# STM32F4.net
KiCad netlist of a schematic drawn in Altium Designer
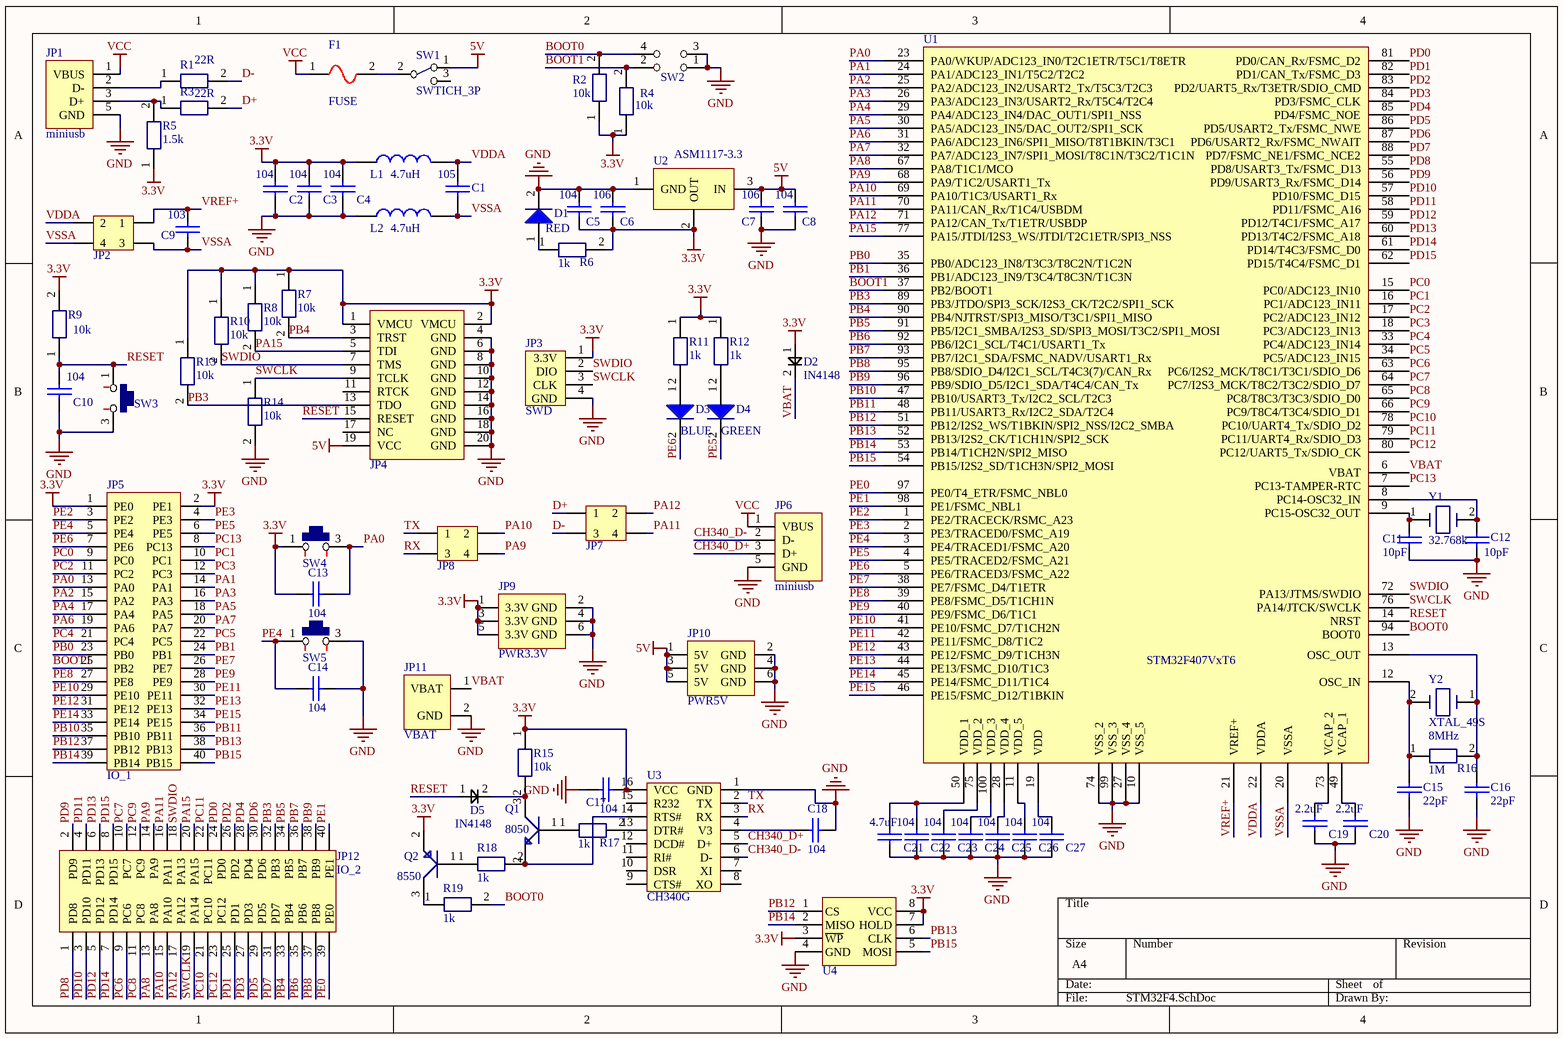
[diagram p0: STM32F4.SchDoc]

(export (version "E")
  (design (tool "Eeschema 10.0.6"))
  (components
    (comp (ref "C1")
      (value "0805c")
      (footprint "0805C")
      (fields (field (name "ALTIUM_UNNAMED_3") "105"))
      (libsource (lib "CORE") (part "0805c"))
    )
    (comp (ref "C2")
      (value "0805c")
      (footprint "0805C")
      (fields (field (name "ALTIUM_UNNAMED_2") "104"))
      (libsource (lib "CORE") (part "0805c"))
    )
    (comp (ref "C3")
      (value "0805c")
      (footprint "0805C")
      (fields (field (name "ALTIUM_UNNAMED_2") "104"))
      (libsource (lib "CORE") (part "0805c"))
    )
    (comp (ref "C4")
      (value "0805c")
      (footprint "0805C")
      (fields (field (name "ALTIUM_UNNAMED_2") "104"))
      (libsource (lib "CORE") (part "0805c"))
    )
    (comp (ref "C5")
      (value "0805c")
      (footprint "0805C")
      (fields (field (name "ALTIUM_UNNAMED_2") "104"))
      (libsource (lib "CORE") (part "0805c"))
    )
    (comp (ref "C6")
      (value "0805c")
      (footprint "0805C")
      (fields (field (name "ALTIUM_UNNAMED_3") "106"))
      (libsource (lib "CORE") (part "0805c"))
    )
    (comp (ref "C7")
      (value "0805c")
      (footprint "0805C")
      (fields (field (name "ALTIUM_UNNAMED_3") "106"))
      (libsource (lib "CORE") (part "0805c"))
    )
    (comp (ref "C8")
      (value "0805c")
      (footprint "0805C")
      (fields (field (name "ALTIUM_UNNAMED_2") "104"))
      (libsource (lib "CORE") (part "0805c"))
    )
    (comp (ref "C9")
      (value "0805c")
      (footprint "0805C")
      (fields (field (name "ALTIUM_UNNAMED_2") "103"))
      (libsource (lib "CORE") (part "0805c"))
    )
    (comp (ref "C10")
      (value "0805c")
      (footprint "0805C")
      (fields (field (name "ALTIUM_UNNAMED_2") "104"))
      (libsource (lib "CORE") (part "0805c"))
    )
    (comp (ref "C11")
      (value "0805c")
      (footprint "0805C")
      (fields (field (name "ALTIUM_UNNAMED_1") "10pF"))
      (libsource (lib "CORE") (part "0805c"))
    )
    (comp (ref "C12")
      (value "0805c")
      (footprint "0805C")
      (fields (field (name "ALTIUM_UNNAMED_1") "10pF"))
      (libsource (lib "CORE") (part "0805c"))
    )
    (comp (ref "C13")
      (value "0805c")
      (footprint "0805C")
      (fields (field (name "ALTIUM_UNNAMED_2") "104"))
      (libsource (lib "CORE") (part "0805c"))
    )
    (comp (ref "C14")
      (value "0805c")
      (footprint "0805C")
      (fields (field (name "ALTIUM_UNNAMED_2") "104"))
      (libsource (lib "CORE") (part "0805c"))
    )
    (comp (ref "C15")
      (value "0805c")
      (footprint "0805C")
      (fields (field (name "ALTIUM_UNNAMED_1") "22pF"))
      (libsource (lib "CORE") (part "0805c"))
    )
    (comp (ref "C16")
      (value "0805c")
      (footprint "0805C")
      (fields (field (name "ALTIUM_UNNAMED_1") "22pF"))
      (libsource (lib "CORE") (part "0805c"))
    )
    (comp (ref "C17")
      (value "0805c")
      (footprint "0805C")
      (fields (field (name "ALTIUM_UNNAMED_2") "104"))
      (libsource (lib "CORE") (part "0805c"))
    )
    (comp (ref "C18")
      (value "0805c")
      (footprint "0805C")
      (fields (field (name "ALTIUM_UNNAMED_2") "104"))
      (libsource (lib "CORE") (part "0805c"))
    )
    (comp (ref "C19")
      (value "0805c")
      (footprint "0805C")
      (fields (field (name "ALTIUM_UNNAMED_2") "2.2uF"))
      (libsource (lib "CORE") (part "0805c"))
    )
    (comp (ref "C20")
      (value "0805c")
      (footprint "0805C")
      (fields (field (name "ALTIUM_UNNAMED_2") "2.2uF"))
      (libsource (lib "CORE") (part "0805c"))
    )
    (comp (ref "C21")
      (value "0805c")
      (footprint "0805C")
      (fields (field (name "ALTIUM_UNNAMED_2") "4.7uF"))
      (libsource (lib "CORE") (part "0805c"))
    )
    (comp (ref "C22")
      (value "0805c")
      (footprint "0805C")
      (fields (field (name "ALTIUM_UNNAMED_2") "104"))
      (libsource (lib "CORE") (part "0805c"))
    )
    (comp (ref "C23")
      (value "0805c")
      (footprint "0805C")
      (fields (field (name "ALTIUM_UNNAMED_2") "104"))
      (libsource (lib "CORE") (part "0805c"))
    )
    (comp (ref "C24")
      (value "0805c")
      (footprint "0805C")
      (fields (field (name "ALTIUM_UNNAMED_2") "104"))
      (libsource (lib "CORE") (part "0805c"))
    )
    (comp (ref "C25")
      (value "0805c")
      (footprint "0805C")
      (fields (field (name "ALTIUM_UNNAMED_2") "104"))
      (libsource (lib "CORE") (part "0805c"))
    )
    (comp (ref "C26")
      (value "0805c")
      (footprint "0805C")
      (fields (field (name "ALTIUM_UNNAMED_2") "104"))
      (libsource (lib "CORE") (part "0805c"))
    )
    (comp (ref "C27")
      (value "0805c")
      (footprint "0805C")
      (fields (field (name "ALTIUM_UNNAMED_2") "104"))
      (libsource (lib "CORE") (part "0805c"))
    )
    (comp (ref "D1")
      (value "LED")
      (footprint "0805D")
      (fields (field (name "ALTIUM_UNNAMED_1") "RED"))
      (libsource (lib "CORE") (part "LED"))
    )
    (comp (ref "D2")
      (value "0805D")
      (footprint "0805D")
      (fields (field (name "PARAMETER 1") "IN4148"))
      (libsource (lib "CORE") (part "0805D"))
    )
    (comp (ref "D3")
      (value "LED")
      (footprint "0805D")
      (fields (field (name "ALTIUM_UNNAMED_1") "BLUE"))
      (libsource (lib "CORE") (part "LED"))
    )
    (comp (ref "D4")
      (value "LED")
      (footprint "0805D")
      (fields (field (name "ALTIUM_UNNAMED_1") "GREEN"))
      (libsource (lib "CORE") (part "LED"))
    )
    (comp (ref "D5")
      (value "0805D")
      (footprint "0805D")
      (fields (field (name "PARAMETER 1") "IN4148"))
      (libsource (lib "CORE") (part "0805D"))
    )
    (comp (ref "F1") (value "FUSE") (footprint "1206R") (libsource (lib "CORE") (part "FUSE")))
    (comp (ref "JP1") (value "miniusb") (footprint "MINI_USB") (libsource (lib "") (part "miniusb_1")))
    (comp (ref "JP2") (value "2*2") (footprint "CON20VP2R54-2X2TM") (libsource (lib "") (part "2*2_1")))
    (comp (ref "JP3") (value "SWD") (footprint "SWD") (libsource (lib "CORE") (part "SWD")))
    (comp (ref "JP4") (value "JTAG") (footprint "JTAG") (libsource (lib "CORE") (part "JTAG")))
    (comp (ref "JP5") (value "IO_1") (footprint "IO") (libsource (lib "CORE") (part "IO_1")))
    (comp (ref "JP6") (value "miniusb") (footprint "MINI_USB") (libsource (lib "CORE") (part "miniusb")))
    (comp (ref "JP7") (value "2*2") (footprint "CON20VP2R54-2X2TM") (libsource (lib "CORE") (part "2*2")))
    (comp (ref "JP8") (value "2*2") (footprint "CON20VP2R54-2X2TM") (libsource (lib "CORE") (part "2*2")))
    (comp (ref "JP9") (value "PWR3.3V") (footprint "PWR") (libsource (lib "CORE") (part "PWR3.3V")))
    (comp (ref "JP10") (value "PWR5V") (footprint "PWR") (libsource (lib "CORE") (part "PWR5V")))
    (comp (ref "JP11") (value "VBAT") (footprint "VBAT") (libsource (lib "CORE") (part "VBAT")))
    (comp (ref "JP12") (value "IO_2") (footprint "IO") (libsource (lib "CORE") (part "IO_2")))
    (comp (ref "L1")
      (value "0805L")
      (footprint "0805L")
      (fields (field (name "ALTIUM_UNNAMED_1") "4.7uH"))
      (libsource (lib "CORE") (part "0805L"))
    )
    (comp (ref "L2")
      (value "0805L")
      (footprint "0805L")
      (fields (field (name "ALTIUM_UNNAMED_1") "4.7uH"))
      (libsource (lib "CORE") (part "0805L"))
    )
    (comp (ref "Q1") (value "8050") (footprint "SOT23-3") (libsource (lib "CORE") (part "8050")))
    (comp (ref "Q2") (value "8550") (footprint "SOT23-3") (libsource (lib "CORE") (part "8550")))
    (comp (ref "R1")
      (value "0805r")
      (footprint "0805R")
      (fields (field (name "ALTIUM_UNNAMED_4") "22R"))
      (libsource (lib "CORE") (part "0805r"))
    )
    (comp (ref "R2")
      (value "0805r")
      (footprint "0805R")
      (fields (field (name "ALTIUM_UNNAMED_4") "10k"))
      (libsource (lib "CORE") (part "0805r"))
    )
    (comp (ref "R3")
      (value "0805r")
      (footprint "0805R")
      (fields (field (name "ALTIUM_UNNAMED_4") "22R"))
      (libsource (lib "CORE") (part "0805r"))
    )
    (comp (ref "R4")
      (value "0805r")
      (footprint "0805R")
      (fields (field (name "ALTIUM_UNNAMED_4") "10k"))
      (libsource (lib "CORE") (part "0805r"))
    )
    (comp (ref "R5")
      (value "0805r")
      (footprint "0805R")
      (fields (field (name "ALTIUM_UNNAMED_4") "1.5k"))
      (libsource (lib "CORE") (part "0805r"))
    )
    (comp (ref "R6")
      (value "0805r")
      (footprint "0805R")
      (fields (field (name "ALTIUM_UNNAMED_3") "1k"))
      (libsource (lib "CORE") (part "0805r"))
    )
    (comp (ref "R7")
      (value "0805r")
      (footprint "0805R")
      (fields (field (name "ALTIUM_UNNAMED_3") "10k"))
      (libsource (lib "CORE") (part "0805r"))
    )
    (comp (ref "R8")
      (value "0805r")
      (footprint "0805R")
      (fields (field (name "ALTIUM_UNNAMED_3") "10k"))
      (libsource (lib "CORE") (part "0805r"))
    )
    (comp (ref "R9")
      (value "0805r")
      (footprint "0805R")
      (fields (field (name "ALTIUM_UNNAMED_1") "10k"))
      (libsource (lib "CORE") (part "0805r"))
    )
    (comp (ref "R10")
      (value "0805r")
      (footprint "0805R")
      (fields (field (name "ALTIUM_UNNAMED_3") "10k"))
      (libsource (lib "CORE") (part "0805r"))
    )
    (comp (ref "R11")
      (value "0805r")
      (footprint "0805R")
      (fields (field (name "ALTIUM_UNNAMED_3") "1k"))
      (libsource (lib "CORE") (part "0805r"))
    )
    (comp (ref "R12")
      (value "0805r")
      (footprint "0805R")
      (fields (field (name "ALTIUM_UNNAMED_3") "1k"))
      (libsource (lib "CORE") (part "0805r"))
    )
    (comp (ref "R13")
      (value "0805r")
      (footprint "0805R")
      (fields (field (name "ALTIUM_UNNAMED_3") "10k"))
      (libsource (lib "CORE") (part "0805r"))
    )
    (comp (ref "R14")
      (value "0805r")
      (footprint "0805R")
      (fields (field (name "ALTIUM_UNNAMED_3") "10k"))
      (libsource (lib "CORE") (part "0805r"))
    )
    (comp (ref "R15")
      (value "0805r")
      (footprint "0805R")
      (fields (field (name "ALTIUM_UNNAMED_3") "10k"))
      (libsource (lib "CORE") (part "0805r"))
    )
    (comp (ref "R16")
      (value "0805r")
      (footprint "0805R")
      (fields (field (name "ALTIUM_UNNAMED_3") "1M"))
      (libsource (lib "CORE") (part "0805r"))
    )
    (comp (ref "R17")
      (value "0805r")
      (footprint "0805R")
      (fields (field (name "ALTIUM_UNNAMED_3") "1k"))
      (libsource (lib "CORE") (part "0805r"))
    )
    (comp (ref "R18")
      (value "0805r")
      (footprint "0805R")
      (fields (field (name "ALTIUM_UNNAMED_3") "1k"))
      (libsource (lib "CORE") (part "0805r"))
    )
    (comp (ref "R19")
      (value "0805r")
      (footprint "0805R")
      (fields (field (name "ALTIUM_UNNAMED_3") "1k"))
      (libsource (lib "CORE") (part "0805r"))
    )
    (comp (ref "SW1") (value "SWTICH_3P") (footprint "SWITCH_3P") (libsource (lib "CORE") (part "SWTICH_3P")))
    (comp (ref "SW2") (value "SW_BOOT") (footprint "DAIL-SWITCH") (libsource (lib "CORE") (part "SW_BOOT")))
    (comp (ref "SW3") (value "KEY") (footprint "KEY_4P") (libsource (lib "CORE") (part "KEY_4P")))
    (comp (ref "SW4") (value "KEY") (footprint "KEY_4P") (libsource (lib "") (part "KEY_4P_1")))
    (comp (ref "SW5") (value "KEY") (footprint "KEY_4P") (libsource (lib "") (part "KEY_4P_1")))
    (comp (ref "U1")
      (value "STM32F407VxT6")
      (footprint "LQFP-100_M")
      (libsource (lib "STM32F4") (part "STM32F407VxT6"))
    )
    (comp (ref "U2")
      (value "ASM1117-3.3")
      (footprint "SOT223_N")
      (libsource (lib "CORE") (part "ASM1117-3.3"))
    )
    (comp (ref "U3") (value "CH340G") (footprint "SOP16") (libsource (lib "CORE") (part "CH340G")))
    (comp (ref "U4") (value "25Q64") (footprint "SOP8") (libsource (lib "CORE") (part "25Q64")))
    (comp (ref "Y1") (value "32.768k") (footprint "圆柱晶振2*6") (libsource (lib "CORE") (part "圆柱晶振")))
    (comp (ref "Y2")
      (value "XTAL_49S")
      (footprint "XTAL")
      (fields (field (name "ALTIUM_UNNAMED_1") "8MHz"))
      (libsource (lib "CORE") (part "XTAL_49S"))
    )
  )
  (nets
    (net (code "1") (name "/BOOT0") (class "Default")
      (node (ref "R19") (pin "2") (pinfunction "2_2") (pintype "passive"))
      (node (ref "R2") (pin "2") (pinfunction "2_2") (pintype "passive"))
      (node (ref "SW2") (pin "4") (pinfunction "4_4") (pintype "passive"))
      (node (ref "U1") (pin "94") (pinfunction "BOOT0_94") (pintype "passive"))
    )
    (net (code "2") (name "/BOOT1") (class "Default")
      (node (ref "JP5") (pin "25") (pinfunction "PB2_25") (pintype "passive"))
      (node (ref "R4") (pin "2") (pinfunction "2_2") (pintype "passive"))
      (node (ref "SW2") (pin "2") (pinfunction "2_2") (pintype "passive"))
      (node (ref "U1") (pin "37") (pinfunction "PB2/BOOT1_37") (pintype "passive"))
    )
    (net (code "3") (name "/CH340_D+") (class "Default")
      (node (ref "JP6") (pin "3") (pinfunction "D+_3") (pintype "passive"))
      (node (ref "U3") (pin "5") (pinfunction "D+_5") (pintype "passive"))
    )
    (net (code "4") (name "/CH340_D-") (class "Default")
      (node (ref "JP6") (pin "2") (pinfunction "D-_2") (pintype "passive"))
      (node (ref "U3") (pin "6") (pinfunction "D-_6") (pintype "passive"))
    )
    (net (code "5") (name "/D+") (class "Default")
      (node (ref "JP7") (pin "1") (pinfunction "1_1") (pintype "passive"))
      (node (ref "R3") (pin "2") (pinfunction "2_2") (pintype "passive"))
    )
    (net (code "6") (name "/D-") (class "Default")
      (node (ref "JP7") (pin "3") (pinfunction "3_3") (pintype "passive"))
      (node (ref "R1") (pin "2") (pinfunction "2_2") (pintype "passive"))
    )
    (net (code "7") (name "/PA0") (class "Default")
      (node (ref "C13") (pin "2") (pinfunction "2_2") (pintype "passive"))
      (node (ref "JP5") (pin "13") (pinfunction "PA0_13") (pintype "passive"))
      (node (ref "SW4") (pin "3") (pintype "passive"))
      (node (ref "U1") (pin "23") (pinfunction "PA0/WKUP/ADC123_IN0/T2C1ETR/T5C1/T8ETR_23") (pintype "passive"))
    )
    (net (code "8") (name "/PA1") (class "Default")
      (node (ref "JP5") (pin "14") (pinfunction "PA1_14") (pintype "passive"))
      (node (ref "U1") (pin "24") (pinfunction "PA1/ADC123_IN1/T5C2/T2C2_24") (pintype "passive"))
    )
    (net (code "9") (name "/PA2") (class "Default")
      (node (ref "JP5") (pin "15") (pinfunction "PA2_15") (pintype "passive"))
      (node (ref "U1") (pin "25") (pinfunction "PA2/ADC123_IN2/USART2_Tx/T5C3/T2C3_25") (pintype "passive"))
    )
    (net (code "10") (name "/PA3") (class "Default")
      (node (ref "JP5") (pin "16") (pinfunction "PA3_16") (pintype "passive"))
      (node (ref "U1") (pin "26") (pinfunction "PA3/ADC123_IN3/USART2_Rx/T5C4/T2C4_26") (pintype "passive"))
    )
    (net (code "11") (name "/PA4") (class "Default")
      (node (ref "JP5") (pin "17") (pinfunction "PA4_17") (pintype "passive"))
      (node (ref "U1") (pin "29") (pinfunction "PA4/ADC123_IN4/DAC_OUT1/SPI1_NSS_29") (pintype "passive"))
    )
    (net (code "12") (name "/PA5") (class "Default")
      (node (ref "JP5") (pin "18") (pinfunction "PA5_18") (pintype "passive"))
      (node (ref "U1") (pin "30") (pinfunction "PA5/ADC123_IN5/DAC_OUT2/SPI1_SCK_30") (pintype "passive"))
    )
    (net (code "13") (name "/PA6") (class "Default")
      (node (ref "JP5") (pin "19") (pinfunction "PA6_19") (pintype "passive"))
      (node (ref "U1") (pin "31") (pinfunction "PA6/ADC123_IN6/SPI1_MISO/T8T1BKIN/T3C1_31") (pintype "passive"))
    )
    (net (code "14") (name "/PA7") (class "Default")
      (node (ref "JP5") (pin "20") (pinfunction "PA7_20") (pintype "passive"))
      (node (ref "U1") (pin "32") (pinfunction "PA7/ADC123_IN7/SPI1_MOSI/T8C1N/T3C2/T1C1N_32") (pintype "passive"))
    )
    (net (code "15") (name "/PA8") (class "Default")
      (node (ref "JP12") (pin "13") (pinfunction "PA8_13") (pintype "passive"))
      (node (ref "U1") (pin "67") (pinfunction "PA8/T1C1/MCO_67") (pintype "passive"))
    )
    (net (code "16") (name "/PA9") (class "Default")
      (node (ref "JP12") (pin "14") (pinfunction "PA9_14") (pintype "passive"))
      (node (ref "JP8") (pin "4") (pinfunction "4_4") (pintype "passive"))
      (node (ref "U1") (pin "68") (pinfunction "PA9/T1C2/USART1_Tx_68") (pintype "passive"))
    )
    (net (code "17") (name "/PA10") (class "Default")
      (node (ref "JP12") (pin "15") (pinfunction "PA10_15") (pintype "passive"))
      (node (ref "JP8") (pin "2") (pinfunction "2_2") (pintype "passive"))
      (node (ref "U1") (pin "69") (pinfunction "PA10/T1C3/USART1_Rx_69") (pintype "passive"))
    )
    (net (code "18") (name "/PA11") (class "Default")
      (node (ref "JP12") (pin "16") (pinfunction "PA11_16") (pintype "passive"))
      (node (ref "JP7") (pin "4") (pinfunction "4_4") (pintype "passive"))
      (node (ref "U1") (pin "70") (pinfunction "PA11/CAN_Rx/T1C4/USBDM_70") (pintype "passive"))
    )
    (net (code "19") (name "/PA12") (class "Default")
      (node (ref "JP12") (pin "17") (pinfunction "PA12_17") (pintype "passive"))
      (node (ref "JP7") (pin "2") (pinfunction "2_2") (pintype "passive"))
      (node (ref "U1") (pin "71") (pinfunction "PA12/CAN_Tx/T1ETR/USBDP_71") (pintype "passive"))
    )
    (net (code "20") (name "/PA15") (class "Default")
      (node (ref "JP12") (pin "20") (pinfunction "PA15_20") (pintype "passive"))
      (node (ref "JP4") (pin "5") (pinfunction "TDI_5") (pintype "passive"))
      (node (ref "R8") (pin "2") (pinfunction "2_2") (pintype "passive"))
      (node (ref "U1") (pin "77") (pinfunction "PA15/JTDI/I2S3_WS/JTDI/T2C1ETR/SPI3_NSS_77") (pintype "passive"))
    )
    (net (code "21") (name "/PB0") (class "Default")
      (node (ref "JP5") (pin "23") (pinfunction "PB0_23") (pintype "passive"))
      (node (ref "U1") (pin "35") (pinfunction "PB0/ADC123_IN8/T3C3/T8C2N/T1C2N_35") (pintype "passive"))
    )
    (net (code "22") (name "/PB1") (class "Default")
      (node (ref "JP5") (pin "24") (pinfunction "PB1_24") (pintype "passive"))
      (node (ref "U1") (pin "36") (pinfunction "PB1/ADC123_IN9/T3C4/T8C3N/T1C3N_36") (pintype "passive"))
    )
    (net (code "23") (name "/PB3") (class "Default")
      (node (ref "JP12") (pin "32") (pinfunction "PB3_32") (pintype "passive"))
      (node (ref "JP4") (pin "13") (pinfunction "TDO_13") (pintype "passive"))
      (node (ref "R13") (pin "2") (pinfunction "2_2") (pintype "passive"))
      (node (ref "U1") (pin "89") (pinfunction "PB3/JTDO/SPI3_SCK/I2S3_CK/T2C2/SPI1_SCK_89") (pintype "passive"))
    )
    (net (code "24") (name "/PB4") (class "Default")
      (node (ref "JP12") (pin "33") (pinfunction "PB4_33") (pintype "passive"))
      (node (ref "JP4") (pin "3") (pinfunction "TRST_3") (pintype "passive"))
      (node (ref "R7") (pin "2") (pinfunction "2_2") (pintype "passive"))
      (node (ref "U1") (pin "90") (pinfunction "PB4/NJTRST/SPI3_MISO/T3C1/SPI1_MISO_90") (pintype "passive"))
    )
    (net (code "25") (name "/PB5") (class "Default")
      (node (ref "JP12") (pin "34") (pinfunction "PB5_34") (pintype "passive"))
      (node (ref "U1") (pin "91") (pinfunction "PB5/I2C1_SMBA/I2S3_SD/SPI3_MOSI/T3C2/SPI1_MOSI_91") (pintype "passive"))
    )
    (net (code "26") (name "/PB6") (class "Default")
      (node (ref "JP12") (pin "35") (pinfunction "PB6_35") (pintype "passive"))
      (node (ref "U1") (pin "92") (pinfunction "PB6/I2C1_SCL/T4C1/USART1_Tx_92") (pintype "passive"))
    )
    (net (code "27") (name "/PB7") (class "Default")
      (node (ref "JP12") (pin "36") (pinfunction "PB7_36") (pintype "passive"))
      (node (ref "U1") (pin "93") (pinfunction "PB7/I2C1_SDA/FSMC_NADV/USART1_Rx_93") (pintype "passive"))
    )
    (net (code "28") (name "/PB8") (class "Default")
      (node (ref "JP12") (pin "37") (pinfunction "PB8_37") (pintype "passive"))
      (node (ref "U1") (pin "95") (pinfunction "PB8/SDIO_D4/I2C1_SCL/T4C3(7)/CAN_Rx_95") (pintype "passive"))
    )
    (net (code "29") (name "/PB9") (class "Default")
      (node (ref "JP12") (pin "38") (pinfunction "PB9_38") (pintype "passive"))
      (node (ref "U1") (pin "96") (pinfunction "PB9/SDIO_D5/I2C1_SDA/T4C4/CAN_Tx_96") (pintype "passive"))
    )
    (net (code "30") (name "/PB10") (class "Default")
      (node (ref "JP5") (pin "35") (pinfunction "PB10_35") (pintype "passive"))
      (node (ref "U1") (pin "47") (pinfunction "PB10/USART3_Tx/I2C2_SCL/T2C3_47") (pintype "passive"))
    )
    (net (code "31") (name "/PB11") (class "Default")
      (node (ref "JP5") (pin "36") (pinfunction "PB11_36") (pintype "passive"))
      (node (ref "U1") (pin "48") (pinfunction "PB11/USART3_Rx/I2C2_SDA/T2C4_48") (pintype "passive"))
    )
    (net (code "32") (name "/PB12") (class "Default")
      (node (ref "JP5") (pin "37") (pinfunction "PB12_37") (pintype "passive"))
      (node (ref "U1") (pin "51") (pinfunction "PB12/I2S2_WS/T1BKIN/SPI2_NSS/I2C2_SMBA_51") (pintype "passive"))
      (node (ref "U4") (pin "1") (pinfunction "CS_1") (pintype "passive"))
    )
    (net (code "33") (name "/PB13") (class "Default")
      (node (ref "JP5") (pin "38") (pinfunction "PB13_38") (pintype "passive"))
      (node (ref "U1") (pin "52") (pinfunction "PB13/I2S2_CK/T1CH1N/SPI2_SCK_52") (pintype "passive"))
      (node (ref "U4") (pin "6") (pinfunction "CLK_6") (pintype "passive"))
    )
    (net (code "34") (name "/PB14") (class "Default")
      (node (ref "JP5") (pin "39") (pinfunction "PB14_39") (pintype "passive"))
      (node (ref "U1") (pin "53") (pinfunction "PB14/T1CH2N/SPI2_MISO_53") (pintype "passive"))
      (node (ref "U4") (pin "2") (pinfunction "MISO_2") (pintype "passive"))
    )
    (net (code "35") (name "/PB15") (class "Default")
      (node (ref "JP5") (pin "40") (pinfunction "PB15_40") (pintype "passive"))
      (node (ref "U1") (pin "54") (pinfunction "PB15/I2S2_SD/T1CH3N/SPI2_MOSI_54") (pintype "passive"))
      (node (ref "U4") (pin "5") (pinfunction "MOSI_5") (pintype "passive"))
    )
    (net (code "36") (name "/PC0") (class "Default")
      (node (ref "JP5") (pin "9") (pinfunction "PC0_9") (pintype "passive"))
      (node (ref "U1") (pin "15") (pinfunction "PC0/ADC123_IN10_15") (pintype "passive"))
    )
    (net (code "37") (name "/PC1") (class "Default")
      (node (ref "JP5") (pin "10") (pinfunction "PC1_10") (pintype "passive"))
      (node (ref "U1") (pin "16") (pinfunction "PC1/ADC123_IN11_16") (pintype "passive"))
    )
    (net (code "38") (name "/PC2") (class "Default")
      (node (ref "JP5") (pin "11") (pinfunction "PC2_11") (pintype "passive"))
      (node (ref "U1") (pin "17") (pinfunction "PC2/ADC123_IN12_17") (pintype "passive"))
    )
    (net (code "39") (name "/PC3") (class "Default")
      (node (ref "JP5") (pin "12") (pinfunction "PC3_12") (pintype "passive"))
      (node (ref "U1") (pin "18") (pinfunction "PC3/ADC123_IN13_18") (pintype "passive"))
    )
    (net (code "40") (name "/PC4") (class "Default")
      (node (ref "JP5") (pin "21") (pinfunction "PC4_21") (pintype "passive"))
      (node (ref "U1") (pin "33") (pinfunction "PC4/ADC123_IN14_33") (pintype "passive"))
    )
    (net (code "41") (name "/PC5") (class "Default")
      (node (ref "JP5") (pin "22") (pinfunction "PC5_22") (pintype "passive"))
      (node (ref "U1") (pin "34") (pinfunction "PC5/ADC123_IN15_34") (pintype "passive"))
    )
    (net (code "42") (name "/PC6") (class "Default")
      (node (ref "JP12") (pin "9") (pinfunction "PC6_9") (pintype "passive"))
      (node (ref "U1") (pin "63") (pinfunction "PC6/I2S2_MCK/T8C1/T3C1/SDIO_D6_63") (pintype "passive"))
    )
    (net (code "43") (name "/PC7") (class "Default")
      (node (ref "JP12") (pin "10") (pinfunction "PC7_10") (pintype "passive"))
      (node (ref "U1") (pin "64") (pinfunction "PC7/I2S3_MCK/T8C2/T3C2/SDIO_D7_64") (pintype "passive"))
    )
    (net (code "44") (name "/PC8") (class "Default")
      (node (ref "JP12") (pin "11") (pinfunction "PC8_11") (pintype "passive"))
      (node (ref "U1") (pin "65") (pinfunction "PC8/T8C3/T3C3/SDIO_D0_65") (pintype "passive"))
    )
    (net (code "45") (name "/PC9") (class "Default")
      (node (ref "JP12") (pin "12") (pinfunction "PC9_12") (pintype "passive"))
      (node (ref "U1") (pin "66") (pinfunction "PC9/T8C4/T3C4/SDIO_D1_66") (pintype "passive"))
    )
    (net (code "46") (name "/PC10") (class "Default")
      (node (ref "JP12") (pin "21") (pinfunction "PC10_21") (pintype "passive"))
      (node (ref "U1") (pin "78") (pinfunction "PC10/UART4_Tx/SDIO_D2_78") (pintype "passive"))
    )
    (net (code "47") (name "/PC11") (class "Default")
      (node (ref "JP12") (pin "22") (pinfunction "PC11_22") (pintype "passive"))
      (node (ref "U1") (pin "79") (pinfunction "PC11/UART4_Rx/SDIO_D3_79") (pintype "passive"))
    )
    (net (code "48") (name "/PC12") (class "Default")
      (node (ref "JP12") (pin "23") (pinfunction "PC12_23") (pintype "passive"))
      (node (ref "U1") (pin "80") (pinfunction "PC12/UART5_Tx/SDIO_CK_80") (pintype "passive"))
    )
    (net (code "49") (name "/PC13") (class "Default")
      (node (ref "JP5") (pin "8") (pinfunction "PC13_8") (pintype "passive"))
      (node (ref "U1") (pin "7") (pinfunction "PC13-TAMPER-RTC_7") (pintype "passive"))
    )
    (net (code "50") (name "/PD0") (class "Default")
      (node (ref "JP12") (pin "24") (pinfunction "PD0_24") (pintype "passive"))
      (node (ref "U1") (pin "81") (pinfunction "PD0/CAN_Rx/FSMC_D2_81") (pintype "passive"))
    )
    (net (code "51") (name "/PD1") (class "Default")
      (node (ref "JP12") (pin "25") (pinfunction "PD1_25") (pintype "passive"))
      (node (ref "U1") (pin "82") (pinfunction "PD1/CAN_Tx/FSMC_D3_82") (pintype "passive"))
    )
    (net (code "52") (name "/PD2") (class "Default")
      (node (ref "JP12") (pin "26") (pinfunction "PD2_26") (pintype "passive"))
      (node (ref "U1") (pin "83") (pinfunction "PD2/UART5_Rx/T3ETR/SDIO_CMD_83") (pintype "passive"))
    )
    (net (code "53") (name "/PD3") (class "Default")
      (node (ref "JP12") (pin "27") (pinfunction "PD3_27") (pintype "passive"))
      (node (ref "U1") (pin "84") (pinfunction "PD3/FSMC_CLK_84") (pintype "passive"))
    )
    (net (code "54") (name "/PD4") (class "Default")
      (node (ref "JP12") (pin "28") (pinfunction "PD4_28") (pintype "passive"))
      (node (ref "U1") (pin "85") (pinfunction "PD4/FSMC_NOE_85") (pintype "passive"))
    )
    (net (code "55") (name "/PD5") (class "Default")
      (node (ref "JP12") (pin "29") (pinfunction "PD5_29") (pintype "passive"))
      (node (ref "U1") (pin "86") (pinfunction "PD5/USART2_Tx/FSMC_NWE_86") (pintype "passive"))
    )
    (net (code "56") (name "/PD6") (class "Default")
      (node (ref "JP12") (pin "30") (pinfunction "PD6_30") (pintype "passive"))
      (node (ref "U1") (pin "87") (pinfunction "PD6/USART2_Rx/FSMC_NWAIT_87") (pintype "passive"))
    )
    (net (code "57") (name "/PD7") (class "Default")
      (node (ref "JP12") (pin "31") (pinfunction "PD7_31") (pintype "passive"))
      (node (ref "U1") (pin "88") (pinfunction "PD7/FSMC_NE1/FSMC_NCE2_88") (pintype "passive"))
    )
    (net (code "58") (name "/PD8") (class "Default")
      (node (ref "JP12") (pin "1") (pinfunction "PD8_1") (pintype "passive"))
      (node (ref "U1") (pin "55") (pinfunction "PD8/USART3_Tx/FSMC_D13_55") (pintype "passive"))
    )
    (net (code "59") (name "/PD9") (class "Default")
      (node (ref "JP12") (pin "2") (pinfunction "PD9_2") (pintype "passive"))
      (node (ref "U1") (pin "56") (pinfunction "PD9/USART3_Rx/FSMC_D14_56") (pintype "passive"))
    )
    (net (code "60") (name "/PD10") (class "Default")
      (node (ref "JP12") (pin "3") (pinfunction "PD10_3") (pintype "passive"))
      (node (ref "U1") (pin "57") (pinfunction "PD10/FSMC_D15_57") (pintype "passive"))
    )
    (net (code "61") (name "/PD11") (class "Default")
      (node (ref "JP12") (pin "4") (pinfunction "PD11_4") (pintype "passive"))
      (node (ref "U1") (pin "58") (pinfunction "PD11/FSMC_A16_58") (pintype "passive"))
    )
    (net (code "62") (name "/PD12") (class "Default")
      (node (ref "JP12") (pin "5") (pinfunction "PD12_5") (pintype "passive"))
      (node (ref "U1") (pin "59") (pinfunction "PD12/T4C1/FSMC_A17_59") (pintype "passive"))
    )
    (net (code "63") (name "/PD13") (class "Default")
      (node (ref "JP12") (pin "6") (pinfunction "PD13_6") (pintype "passive"))
      (node (ref "U1") (pin "60") (pinfunction "PD13/T4C2/FSMC_A18_60") (pintype "passive"))
    )
    (net (code "64") (name "/PD14") (class "Default")
      (node (ref "JP12") (pin "7") (pinfunction "PD14_7") (pintype "passive"))
      (node (ref "U1") (pin "61") (pinfunction "PD14/T4C3/FSMC_D0_61") (pintype "passive"))
    )
    (net (code "65") (name "/PD15") (class "Default")
      (node (ref "JP12") (pin "8") (pinfunction "PD15_8") (pintype "passive"))
      (node (ref "U1") (pin "62") (pinfunction "PD15/T4C4/FSMC_D1_62") (pintype "passive"))
    )
    (net (code "66") (name "/PE0") (class "Default")
      (node (ref "JP12") (pin "39") (pinfunction "PE0_39") (pintype "passive"))
      (node (ref "U1") (pin "97") (pinfunction "PE0/T4_ETR/FSMC_NBL0_97") (pintype "passive"))
    )
    (net (code "67") (name "/PE1") (class "Default")
      (node (ref "JP12") (pin "40") (pinfunction "PE1_40") (pintype "passive"))
      (node (ref "U1") (pin "98") (pinfunction "PE1/FSMC_NBL1_98") (pintype "passive"))
    )
    (net (code "68") (name "/PE2") (class "Default")
      (node (ref "JP5") (pin "3") (pinfunction "PE2_3") (pintype "passive"))
      (node (ref "U1") (pin "1") (pinfunction "PE2/TRACECK/RSMC_A23_1") (pintype "passive"))
    )
    (net (code "69") (name "/PE3") (class "Default")
      (node (ref "JP5") (pin "4") (pinfunction "PE3_4") (pintype "passive"))
      (node (ref "U1") (pin "2") (pinfunction "PE3/TRACED0/FSMC_A19_2") (pintype "passive"))
    )
    (net (code "70") (name "/PE4") (class "Default")
      (node (ref "C14") (pin "1") (pinfunction "1_1") (pintype "passive"))
      (node (ref "JP5") (pin "5") (pinfunction "PE4_5") (pintype "passive"))
      (node (ref "SW5") (pin "1") (pintype "passive"))
      (node (ref "U1") (pin "3") (pinfunction "PE4/TRACED1/FSMC_A20_3") (pintype "passive"))
    )
    (net (code "71") (name "/PE5") (class "Default")
      (node (ref "D4") (pin "2") (pinfunction "2_2") (pintype "passive"))
      (node (ref "JP5") (pin "6") (pinfunction "PE5_6") (pintype "passive"))
      (node (ref "U1") (pin "4") (pinfunction "PE5/TRACED2/FSMC_A21_4") (pintype "passive"))
    )
    (net (code "72") (name "/PE6") (class "Default")
      (node (ref "D3") (pin "2") (pinfunction "2_2") (pintype "passive"))
      (node (ref "JP5") (pin "7") (pinfunction "PE6_7") (pintype "passive"))
      (node (ref "U1") (pin "5") (pinfunction "PE6/TRACED3/FSMC_A22_5") (pintype "passive"))
    )
    (net (code "73") (name "/PE7") (class "Default")
      (node (ref "JP5") (pin "26") (pinfunction "PE7_26") (pintype "passive"))
      (node (ref "U1") (pin "38") (pinfunction "PE7/FSMC_D4/T1ETR_38") (pintype "passive"))
    )
    (net (code "74") (name "/PE8") (class "Default")
      (node (ref "JP5") (pin "27") (pinfunction "PE8_27") (pintype "passive"))
      (node (ref "U1") (pin "39") (pinfunction "PE8/FSMC_D5/T1CH1N_39") (pintype "passive"))
    )
    (net (code "75") (name "/PE9") (class "Default")
      (node (ref "JP5") (pin "28") (pinfunction "PE9_28") (pintype "passive"))
      (node (ref "U1") (pin "40") (pinfunction "PE9/FSMC_D6/T1C1_40") (pintype "passive"))
    )
    (net (code "76") (name "/PE10") (class "Default")
      (node (ref "JP5") (pin "29") (pinfunction "PE10_29") (pintype "passive"))
      (node (ref "U1") (pin "41") (pinfunction "PE10/FSMC_D7/T1CH2N_41") (pintype "passive"))
    )
    (net (code "77") (name "/PE11") (class "Default")
      (node (ref "JP5") (pin "30") (pinfunction "PE11_30") (pintype "passive"))
      (node (ref "U1") (pin "42") (pinfunction "PE11/FSMC_D8/T1C2_42") (pintype "passive"))
    )
    (net (code "78") (name "/PE12") (class "Default")
      (node (ref "JP5") (pin "31") (pinfunction "PE12_31") (pintype "passive"))
      (node (ref "U1") (pin "43") (pinfunction "PE12/FSMC_D9/T1CH3N_43") (pintype "passive"))
    )
    (net (code "79") (name "/PE13") (class "Default")
      (node (ref "JP5") (pin "32") (pinfunction "PE13_32") (pintype "passive"))
      (node (ref "U1") (pin "44") (pinfunction "PE13/FSMC_D10/T1C3_44") (pintype "passive"))
    )
    (net (code "80") (name "/PE14") (class "Default")
      (node (ref "JP5") (pin "33") (pinfunction "PE14_33") (pintype "passive"))
      (node (ref "U1") (pin "45") (pinfunction "PE14/FSMC_D11/T1C4_45") (pintype "passive"))
    )
    (net (code "81") (name "/PE15") (class "Default")
      (node (ref "JP5") (pin "34") (pinfunction "PE15_34") (pintype "passive"))
      (node (ref "U1") (pin "46") (pinfunction "PE15/FSMC_D12/T1BKIN_46") (pintype "passive"))
    )
    (net (code "82") (name "/RESET") (class "Default")
      (node (ref "C10") (pin "1") (pinfunction "1_1") (pintype "passive"))
      (node (ref "D5") (pin "1") (pinfunction "3_1") (pintype "passive"))
      (node (ref "JP4") (pin "15") (pinfunction "RESET_15") (pintype "passive"))
      (node (ref "R9") (pin "1") (pinfunction "1_1") (pintype "passive"))
      (node (ref "SW3") (pin "1") (pintype "passive"))
      (node (ref "U1") (pin "14") (pinfunction "NRST_14") (pintype "passive"))
    )
    (net (code "83") (name "/RX") (class "Default")
      (node (ref "JP8") (pin "3") (pinfunction "3_3") (pintype "passive"))
      (node (ref "U3") (pin "3") (pinfunction "RX_3") (pintype "passive"))
    )
    (net (code "84") (name "/SWCLK") (class "Default")
      (node (ref "JP12") (pin "19") (pinfunction "PA14_19") (pintype "passive"))
      (node (ref "JP3") (pin "3") (pinfunction "CLK_3") (pintype "passive"))
      (node (ref "JP4") (pin "9") (pinfunction "TCLK_9") (pintype "passive"))
      (node (ref "R14") (pin "1") (pinfunction "1_1") (pintype "passive"))
      (node (ref "U1") (pin "76") (pinfunction "PA14/JTCK/SWCLK_76") (pintype "passive"))
    )
    (net (code "85") (name "/SWDIO") (class "Default")
      (node (ref "JP12") (pin "18") (pinfunction "PA13_18") (pintype "passive"))
      (node (ref "JP3") (pin "2") (pinfunction "DIO_2") (pintype "passive"))
      (node (ref "JP4") (pin "7") (pinfunction "TMS_7") (pintype "passive"))
      (node (ref "R10") (pin "2") (pinfunction "2_2") (pintype "passive"))
      (node (ref "U1") (pin "72") (pinfunction "PA13/JTMS/SWDIO_72") (pintype "passive"))
    )
    (net (code "86") (name "/TX") (class "Default")
      (node (ref "JP8") (pin "1") (pinfunction "1_1") (pintype "passive"))
      (node (ref "U3") (pin "2") (pinfunction "TX_2") (pintype "passive"))
    )
    (net (code "87") (name "/VBAT") (class "Default")
      (node (ref "D2") (pin "2") (pinfunction "2_2") (pintype "passive"))
      (node (ref "JP11") (pin "1") (pinfunction "VBAT_1") (pintype "passive"))
      (node (ref "U1") (pin "6") (pinfunction "VBAT_6") (pintype "passive"))
    )
    (net (code "88") (name "/VDDA") (class "Default")
      (node (ref "C1") (pin "1") (pinfunction "1_1") (pintype "passive"))
      (node (ref "JP2") (pin "2") (pinfunction "2_2") (pintype "passive"))
      (node (ref "L1") (pin "2") (pinfunction "2_2") (pintype "passive"))
      (node (ref "U1") (pin "22") (pinfunction "VDDA_22") (pintype "passive"))
    )
    (net (code "89") (name "/VREF+") (class "Default")
      (node (ref "C9") (pin "1") (pinfunction "1_1") (pintype "passive"))
      (node (ref "JP2") (pin "1") (pinfunction "1_1") (pintype "passive"))
      (node (ref "U1") (pin "21") (pinfunction "VREF+_21") (pintype "passive"))
    )
    (net (code "90") (name "/VSSA") (class "Default")
      (node (ref "C1") (pin "2") (pinfunction "2_2") (pintype "passive"))
      (node (ref "C9") (pin "2") (pinfunction "2_2") (pintype "passive"))
      (node (ref "JP2") (pin "3") (pinfunction "3_3") (pintype "passive"))
      (node (ref "JP2") (pin "4") (pinfunction "4_4") (pintype "passive"))
      (node (ref "L2") (pin "2") (pinfunction "2_2") (pintype "passive"))
      (node (ref "U1") (pin "20") (pinfunction "VSSA_20") (pintype "passive"))
    )
    (net (code "91") (name "3.3V") (class "Default")
      (node (ref "C13") (pin "1") (pinfunction "1_1") (pintype "passive"))
      (node (ref "C17") (pin "2") (pinfunction "2_2") (pintype "passive"))
      (node (ref "C2") (pin "1") (pinfunction "1_1") (pintype "passive"))
      (node (ref "C3") (pin "1") (pinfunction "1_1") (pintype "passive"))
      (node (ref "C4") (pin "1") (pinfunction "1_1") (pintype "passive"))
      (node (ref "C5") (pin "2") (pinfunction "2_2") (pintype "passive"))
      (node (ref "C6") (pin "2") (pinfunction "2_2") (pintype "passive"))
      (node (ref "D2") (pin "1") (pinfunction "3_1") (pintype "passive"))
      (node (ref "JP3") (pin "1") (pinfunction "3.3V_1") (pintype "passive"))
      (node (ref "JP4") (pin "1") (pinfunction "VMCU_1") (pintype "passive"))
      (node (ref "JP4") (pin "2") (pinfunction "VMCU_2") (pintype "passive"))
      (node (ref "JP5") (pin "1") (pinfunction "PE0_1") (pintype "passive"))
      (node (ref "JP5") (pin "2") (pinfunction "PE1_2") (pintype "passive"))
      (node (ref "JP9") (pin "1") (pinfunction "3.3V_1") (pintype "passive"))
      (node (ref "JP9") (pin "3") (pinfunction "3.3V_3") (pintype "passive"))
      (node (ref "JP9") (pin "5") (pinfunction "3.3V_5") (pintype "passive"))
      (node (ref "L1") (pin "1") (pinfunction "1_1") (pintype "passive"))
      (node (ref "Q2") (pin "2") (pinfunction "E_2") (pintype "passive"))
      (node (ref "R10") (pin "1") (pinfunction "1_1") (pintype "passive"))
      (node (ref "R11") (pin "1") (pinfunction "1_1") (pintype "passive"))
      (node (ref "R12") (pin "1") (pinfunction "1_1") (pintype "passive"))
      (node (ref "R13") (pin "1") (pinfunction "1_1") (pintype "passive"))
      (node (ref "R15") (pin "1") (pinfunction "1_1") (pintype "passive"))
      (node (ref "R2") (pin "1") (pinfunction "1_1") (pintype "passive"))
      (node (ref "R4") (pin "1") (pinfunction "1_1") (pintype "passive"))
      (node (ref "R5") (pin "1") (pinfunction "1_1") (pintype "passive"))
      (node (ref "R6") (pin "2") (pinfunction "2_2") (pintype "passive"))
      (node (ref "R7") (pin "1") (pinfunction "1_1") (pintype "passive"))
      (node (ref "R8") (pin "1") (pinfunction "1_1") (pintype "passive"))
      (node (ref "R9") (pin "2") (pinfunction "2_2") (pintype "passive"))
      (node (ref "SW4") (pin "1") (pintype "passive"))
      (node (ref "U2") (pin "2") (pinfunction "OUT_2") (pintype "passive"))
      (node (ref "U3") (pin "16") (pinfunction "VCC_16") (pintype "passive"))
      (node (ref "U4") (pin "3") (pinfunction "~{WP}_3") (pintype "passive"))
      (node (ref "U4") (pin "7") (pinfunction "HOLD_7") (pintype "passive"))
      (node (ref "U4") (pin "8") (pinfunction "VCC_8") (pintype "passive"))
    )
    (net (code "92") (name "5V") (class "Default")
      (node (ref "C7") (pin "1") (pinfunction "1_1") (pintype "passive"))
      (node (ref "C8") (pin "1") (pinfunction "1_1") (pintype "passive"))
      (node (ref "JP10") (pin "1") (pinfunction "5V_1") (pintype "passive"))
      (node (ref "JP10") (pin "3") (pinfunction "5V_3") (pintype "passive"))
      (node (ref "JP10") (pin "5") (pinfunction "5V_5") (pintype "passive"))
      (node (ref "JP4") (pin "19") (pinfunction "VCC_19") (pintype "passive"))
      (node (ref "SW1") (pin "1") (pinfunction "1_1") (pintype "passive"))
      (node (ref "U2") (pin "3") (pinfunction "IN_3") (pintype "passive"))
    )
    (net (code "93") (name "GND") (class "Default")
      (node (ref "C10") (pin "2") (pinfunction "2_2") (pintype "passive"))
      (node (ref "C11") (pin "2") (pinfunction "2_2") (pintype "passive"))
      (node (ref "C12") (pin "2") (pinfunction "2_2") (pintype "passive"))
      (node (ref "C14") (pin "2") (pinfunction "2_2") (pintype "passive"))
      (node (ref "C15") (pin "2") (pinfunction "2_2") (pintype "passive"))
      (node (ref "C16") (pin "2") (pinfunction "2_2") (pintype "passive"))
      (node (ref "C17") (pin "1") (pinfunction "1_1") (pintype "passive"))
      (node (ref "C18") (pin "2") (pinfunction "2_2") (pintype "passive"))
      (node (ref "C19") (pin "2") (pinfunction "2_2") (pintype "passive"))
      (node (ref "C2") (pin "2") (pinfunction "2_2") (pintype "passive"))
      (node (ref "C20") (pin "2") (pinfunction "2_2") (pintype "passive"))
      (node (ref "C21") (pin "2") (pinfunction "2_2") (pintype "passive"))
      (node (ref "C22") (pin "2") (pinfunction "2_2") (pintype "passive"))
      (node (ref "C23") (pin "2") (pinfunction "2_2") (pintype "passive"))
      (node (ref "C24") (pin "2") (pinfunction "2_2") (pintype "passive"))
      (node (ref "C25") (pin "2") (pinfunction "2_2") (pintype "passive"))
      (node (ref "C26") (pin "2") (pinfunction "2_2") (pintype "passive"))
      (node (ref "C27") (pin "2") (pinfunction "2_2") (pintype "passive"))
      (node (ref "C3") (pin "2") (pinfunction "2_2") (pintype "passive"))
      (node (ref "C4") (pin "2") (pinfunction "2_2") (pintype "passive"))
      (node (ref "C5") (pin "1") (pinfunction "1_1") (pintype "passive"))
      (node (ref "C6") (pin "1") (pinfunction "1_1") (pintype "passive"))
      (node (ref "C7") (pin "2") (pinfunction "2_2") (pintype "passive"))
      (node (ref "C8") (pin "2") (pinfunction "2_2") (pintype "passive"))
      (node (ref "D1") (pin "2") (pinfunction "2_2") (pintype "passive"))
      (node (ref "JP1") (pin "5") (pinfunction "GND_5") (pintype "passive"))
      (node (ref "JP10") (pin "2") (pinfunction "GND_2") (pintype "passive"))
      (node (ref "JP10") (pin "4") (pinfunction "GND_4") (pintype "passive"))
      (node (ref "JP10") (pin "6") (pinfunction "GND_6") (pintype "passive"))
      (node (ref "JP11") (pin "2") (pinfunction "GND_2") (pintype "passive"))
      (node (ref "JP3") (pin "4") (pinfunction "GND_4") (pintype "passive"))
      (node (ref "JP4") (pin "10") (pinfunction "GND_10") (pintype "passive"))
      (node (ref "JP4") (pin "12") (pinfunction "GND_12") (pintype "passive"))
      (node (ref "JP4") (pin "14") (pinfunction "GND_14") (pintype "passive"))
      (node (ref "JP4") (pin "16") (pinfunction "GND_16") (pintype "passive"))
      (node (ref "JP4") (pin "18") (pinfunction "GND_18") (pintype "passive"))
      (node (ref "JP4") (pin "20") (pinfunction "GND_20") (pintype "passive"))
      (node (ref "JP4") (pin "4") (pinfunction "GND_4") (pintype "passive"))
      (node (ref "JP4") (pin "6") (pinfunction "GND_6") (pintype "passive"))
      (node (ref "JP4") (pin "8") (pinfunction "GND_8") (pintype "passive"))
      (node (ref "JP6") (pin "5") (pinfunction "GND_5") (pintype "passive"))
      (node (ref "JP9") (pin "2") (pinfunction "GND_2") (pintype "passive"))
      (node (ref "JP9") (pin "4") (pinfunction "GND_4") (pintype "passive"))
      (node (ref "JP9") (pin "6") (pinfunction "GND_6") (pintype "passive"))
      (node (ref "L2") (pin "1") (pinfunction "1_1") (pintype "passive"))
      (node (ref "R14") (pin "2") (pinfunction "2_2") (pintype "passive"))
      (node (ref "SW2") (pin "1") (pinfunction "1_1") (pintype "passive"))
      (node (ref "SW2") (pin "3") (pinfunction "3_3") (pintype "passive"))
      (node (ref "SW3") (pin "3") (pintype "passive"))
      (node (ref "SW5") (pin "3") (pintype "passive"))
      (node (ref "U1") (pin "10") (pinfunction "VSS_5_10") (pintype "passive"))
      (node (ref "U1") (pin "27") (pinfunction "VSS_4_27") (pintype "passive"))
      (node (ref "U1") (pin "74") (pinfunction "VSS_2_74") (pintype "passive"))
      (node (ref "U1") (pin "99") (pinfunction "VSS_3_99") (pintype "passive"))
      (node (ref "U2") (pin "1") (pinfunction "GND_1") (pintype "passive"))
      (node (ref "U3") (pin "1") (pinfunction "GND_1") (pintype "passive"))
      (node (ref "U4") (pin "4") (pinfunction "GND_4") (pintype "passive"))
    )
    (net (code "94") (name "Net-(D1-Pad1)") (class "Default")
      (node (ref "D1") (pin "1") (pinfunction "1_1") (pintype "passive"))
      (node (ref "R6") (pin "1") (pinfunction "1_1") (pintype "passive"))
    )
    (net (code "95") (name "Net-(D3-Pad1)") (class "Default")
      (node (ref "D3") (pin "1") (pinfunction "1_1") (pintype "passive"))
      (node (ref "R11") (pin "2") (pinfunction "2_2") (pintype "passive"))
    )
    (net (code "96") (name "Net-(D4-Pad1)") (class "Default")
      (node (ref "D4") (pin "1") (pinfunction "1_1") (pintype "passive"))
      (node (ref "R12") (pin "2") (pinfunction "2_2") (pintype "passive"))
    )
    (net (code "97") (name "Net-(F1-Pad2)") (class "Default")
      (node (ref "F1") (pin "2") (pinfunction "2_2") (pintype "passive"))
      (node (ref "SW1") (pin "2") (pinfunction "2_2") (pintype "passive"))
    )
    (net (code "98") (name "Net-(JP1-D+)") (class "Default")
      (node (ref "JP1") (pin "3") (pinfunction "D+_3") (pintype "passive"))
      (node (ref "R3") (pin "1") (pinfunction "1_1") (pintype "passive"))
      (node (ref "R5") (pin "2") (pinfunction "2_2") (pintype "passive"))
    )
    (net (code "99") (name "Net-(JP1-D-)") (class "Default")
      (node (ref "JP1") (pin "2") (pinfunction "D-_2") (pintype "passive"))
      (node (ref "R1") (pin "1") (pinfunction "1_1") (pintype "passive"))
    )
    (net (code "100") (name "Net-(Q1-B)") (class "Default")
      (node (ref "Q1") (pin "1") (pinfunction "B_1") (pintype "passive"))
      (node (ref "R17") (pin "1") (pinfunction "1_1") (pintype "passive"))
    )
    (net (code "101") (name "Net-(Q1-C)") (class "Default")
      (node (ref "D5") (pin "2") (pinfunction "2_2") (pintype "passive"))
      (node (ref "Q1") (pin "3") (pinfunction "C_3") (pintype "passive"))
      (node (ref "R15") (pin "2") (pinfunction "2_2") (pintype "passive"))
    )
    (net (code "102") (name "Net-(Q1-E)") (class "Default")
      (node (ref "Q1") (pin "2") (pinfunction "E_2") (pintype "passive"))
      (node (ref "R18") (pin "2") (pinfunction "2_2") (pintype "passive"))
      (node (ref "U3") (pin "14") (pinfunction "RTS#_14") (pintype "passive"))
    )
    (net (code "103") (name "Net-(Q2-B)") (class "Default")
      (node (ref "Q2") (pin "1") (pinfunction "B_1") (pintype "passive"))
      (node (ref "R18") (pin "1") (pinfunction "1_1") (pintype "passive"))
    )
    (net (code "104") (name "Net-(Q2-C)") (class "Default")
      (node (ref "Q2") (pin "3") (pinfunction "C_3") (pintype "passive"))
      (node (ref "R19") (pin "1") (pinfunction "1_1") (pintype "passive"))
    )
    (net (code "105") (name "Net-(U1-OSC_IN)") (class "Default")
      (node (ref "C15") (pin "1") (pinfunction "1_1") (pintype "passive"))
      (node (ref "R16") (pin "1") (pinfunction "1_1") (pintype "passive"))
      (node (ref "U1") (pin "12") (pinfunction "OSC_IN_12") (pintype "passive"))
      (node (ref "Y2") (pin "2") (pinfunction "2_2") (pintype "passive"))
    )
    (net (code "106") (name "Net-(U1-OSC_OUT)") (class "Default")
      (node (ref "C16") (pin "1") (pinfunction "1_1") (pintype "passive"))
      (node (ref "R16") (pin "2") (pinfunction "2_2") (pintype "passive"))
      (node (ref "U1") (pin "13") (pinfunction "OSC_OUT_13") (pintype "passive"))
      (node (ref "Y2") (pin "1") (pinfunction "1_1") (pintype "passive"))
    )
    (net (code "107") (name "Net-(U1-PC14-OSC32_IN)") (class "Default")
      (node (ref "C12") (pin "1") (pinfunction "1_1") (pintype "passive"))
      (node (ref "U1") (pin "8") (pinfunction "PC14-OSC32_IN_8") (pintype "passive"))
      (node (ref "Y1") (pin "2") (pinfunction "2_2") (pintype "passive"))
    )
    (net (code "108") (name "Net-(U1-PC15-OSC32_OUT)") (class "Default")
      (node (ref "C11") (pin "1") (pinfunction "1_1") (pintype "passive"))
      (node (ref "U1") (pin "9") (pinfunction "PC15-OSC32_OUT_9") (pintype "passive"))
      (node (ref "Y1") (pin "1") (pinfunction "1_1") (pintype "passive"))
    )
    (net (code "109") (name "Net-(U1-VCAP_1)") (class "Default")
      (node (ref "C20") (pin "1") (pinfunction "1_1") (pintype "passive"))
      (node (ref "U1") (pin "49") (pinfunction "VCAP_1_49") (pintype "passive"))
    )
    (net (code "110") (name "Net-(U1-VCAP_2)") (class "Default")
      (node (ref "C19") (pin "1") (pinfunction "1_1") (pintype "passive"))
      (node (ref "U1") (pin "73") (pinfunction "VCAP_2_73") (pintype "passive"))
    )
    (net (code "111") (name "Net-(U1-VDD)") (class "Default")
      (node (ref "C27") (pin "1") (pinfunction "1_1") (pintype "passive"))
      (node (ref "U1") (pin "19") (pinfunction "VDD_19") (pintype "passive"))
    )
    (net (code "112") (name "Net-(U1-VDD_1)") (class "Default")
      (node (ref "C21") (pin "1") (pinfunction "1_1") (pintype "passive"))
      (node (ref "C22") (pin "1") (pinfunction "1_1") (pintype "passive"))
      (node (ref "U1") (pin "50") (pinfunction "VDD_1_50") (pintype "passive"))
    )
    (net (code "113") (name "Net-(U1-VDD_2)") (class "Default")
      (node (ref "C23") (pin "1") (pinfunction "1_1") (pintype "passive"))
      (node (ref "U1") (pin "75") (pinfunction "VDD_2_75") (pintype "passive"))
    )
    (net (code "114") (name "Net-(U1-VDD_3)") (class "Default")
      (node (ref "C24") (pin "1") (pinfunction "1_1") (pintype "passive"))
      (node (ref "U1") (pin "100") (pinfunction "VDD_3_100") (pintype "passive"))
    )
    (net (code "115") (name "Net-(U1-VDD_4)") (class "Default")
      (node (ref "C25") (pin "1") (pinfunction "1_1") (pintype "passive"))
      (node (ref "U1") (pin "28") (pinfunction "VDD_4_28") (pintype "passive"))
    )
    (net (code "116") (name "Net-(U1-VDD_5)") (class "Default")
      (node (ref "C26") (pin "1") (pinfunction "1_1") (pintype "passive"))
      (node (ref "U1") (pin "11") (pinfunction "VDD_5_11") (pintype "passive"))
    )
    (net (code "117") (name "Net-(U3-DTR#)") (class "Default")
      (node (ref "R17") (pin "2") (pinfunction "2_2") (pintype "passive"))
      (node (ref "U3") (pin "13") (pinfunction "DTR#_13") (pintype "passive"))
    )
    (net (code "118") (name "Net-(U3-V3)") (class "Default")
      (node (ref "C18") (pin "1") (pinfunction "1_1") (pintype "passive"))
      (node (ref "U3") (pin "4") (pinfunction "V3_4") (pintype "passive"))
    )
    (net (code "119") (name "VCC") (class "Default")
      (node (ref "F1") (pin "1") (pinfunction "1_1") (pintype "passive"))
      (node (ref "JP1") (pin "1") (pinfunction "VBUS_1") (pintype "passive"))
      (node (ref "JP6") (pin "1") (pinfunction "VBUS_1") (pintype "passive"))
    )
    (net (code "120") (name "unconnected-(JP4-NC-Pad17)") (class "Default")
      (node (ref "JP4") (pin "17") (pinfunction "NC_17") (pintype "passive"))
    )
    (net (code "121") (name "unconnected-(JP4-RTCK-Pad11)") (class "Default")
      (node (ref "JP4") (pin "11") (pinfunction "RTCK_11") (pintype "passive"))
    )
    (net (code "122") (name "unconnected-(SW1-Pad3)") (class "Default")
      (node (ref "SW1") (pin "3") (pinfunction "3_3") (pintype "passive"))
    )
    (net (code "123") (name "unconnected-(U3-CTS#-Pad9)") (class "Default")
      (node (ref "U3") (pin "9") (pinfunction "CTS#_9") (pintype "passive"))
    )
    (net (code "124") (name "unconnected-(U3-DCD#-Pad12)") (class "Default")
      (node (ref "U3") (pin "12") (pinfunction "DCD#_12") (pintype "passive"))
    )
    (net (code "125") (name "unconnected-(U3-DSR-Pad10)") (class "Default")
      (node (ref "U3") (pin "10") (pinfunction "DSR_10") (pintype "passive"))
    )
    (net (code "126") (name "unconnected-(U3-R232-Pad15)") (class "Default")
      (node (ref "U3") (pin "15") (pinfunction "R232_15") (pintype "passive"))
    )
    (net (code "127") (name "unconnected-(U3-RI#-Pad11)") (class "Default")
      (node (ref "U3") (pin "11") (pinfunction "RI#_11") (pintype "passive"))
    )
    (net (code "128") (name "unconnected-(U3-XI-Pad7)") (class "Default")
      (node (ref "U3") (pin "7") (pinfunction "XI_7") (pintype "passive"))
    )
    (net (code "129") (name "unconnected-(U3-XO-Pad8)") (class "Default")
      (node (ref "U3") (pin "8") (pinfunction "XO_8") (pintype "passive"))
    )
  )
)
